# DSD_Aerobits_RPI4_OLED.net
KiCad netlist of a schematic drawn in Altium Designer
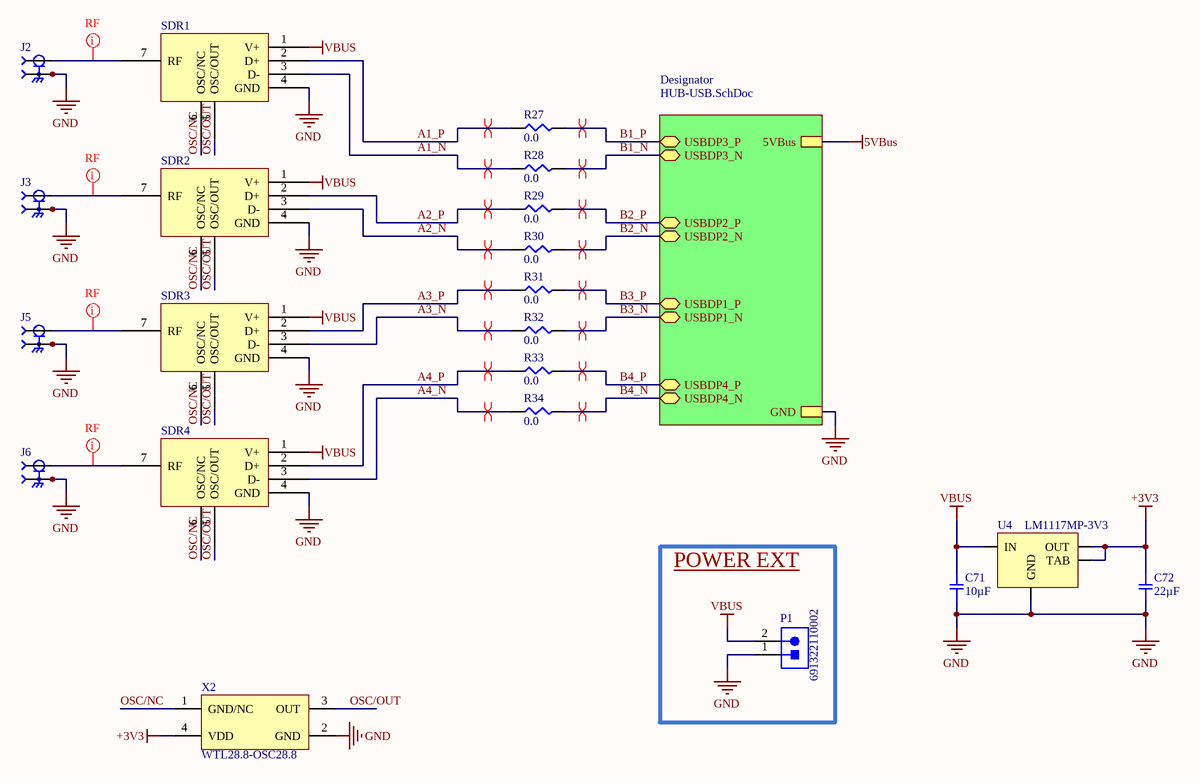
[diagram p0: DSD_Aerobits_RPI4_OLED.SchDoc]

(export (version "E")
  (design (tool "Eeschema 10.0.6"))
  (components
    (comp (ref "C71")
      (value "10µF")
      (footprint "SMD-0805C")
      (description "CAP CER 10UF 16V X6S 0805")
      (fields
        (field (name "PART NUMBER") "GRT21BC81C106KE01L")
        (field (name "DIGI-KEY PART NUMBER") "490-12343-1-ND")
      )
      (libsource (lib "cap_murata") (part "CAPACITOR"))
    )
    (comp (ref "C72")
      (value "22µF")
      (footprint "SMD-0805C")
      (description "CAP CER 22UF 16V X5R 0805")
      (fields
        (field (name "PART NUMBER") "GRT21BR61C226ME13L")
        (field (name "DIGI-KEY PART NUMBER") "490-12383-1-ND")
      )
      (libsource (lib "cap_murata") (part "CAPACITOR"))
    )
    (comp (ref "J2")
      (value "CON-SMA-EDGE-S")
      (footprint "RFSOLUTIONS_CON-SMA-EDGE-S")
      (description "SMA Connector Jack, Female Socket - Board Edge, End Launch Solder")
      (fields (field (name "MF") "RF Solutions") (field (name "DIGI-KEY_PART_NUMBER") "CON-SMA-EDGE-S-ND"))
      (libsource (lib "CON-SMA-EDGE-S") (part "CON-SMA-EDGE-S"))
    )
    (comp (ref "J3")
      (value "CON-SMA-EDGE-S")
      (footprint "RFSOLUTIONS_CON-SMA-EDGE-S")
      (description "SMA Connector Jack, Female Socket - Board Edge, End Launch Solder")
      (fields (field (name "MF") "RF Solutions") (field (name "DIGI-KEY_PART_NUMBER") "CON-SMA-EDGE-S-ND"))
      (libsource (lib "CON-SMA-EDGE-S") (part "CON-SMA-EDGE-S"))
    )
    (comp (ref "J5")
      (value "CON-SMA-EDGE-S")
      (footprint "RFSOLUTIONS_CON-SMA-EDGE-S")
      (description "SMA Connector Jack, Female Socket - Board Edge, End Launch Solder")
      (fields (field (name "MF") "RF Solutions") (field (name "DIGI-KEY_PART_NUMBER") "CON-SMA-EDGE-S-ND"))
      (libsource (lib "CON-SMA-EDGE-S") (part "CON-SMA-EDGE-S"))
    )
    (comp (ref "J6")
      (value "CON-SMA-EDGE-S")
      (footprint "RFSOLUTIONS_CON-SMA-EDGE-S")
      (description "SMA Connector Jack, Female Socket - Board Edge, End Launch Solder")
      (fields (field (name "MF") "RF Solutions") (field (name "DIGI-KEY_PART_NUMBER") "CON-SMA-EDGE-S-ND"))
      (libsource (lib "CON-SMA-EDGE-S") (part "CON-SMA-EDGE-S"))
    )
    (comp (ref "P1")
      (value "691322110002")
      (footprint "691322110002")
      (description "WR-TBL Serie 3221 Horizontal PCB Header, Pluggable, THT, pitch 3.5mm, 2p")
      (fields (field (name "MANUFACTURER") "Wurth Elektronik"))
      (libsource (lib "Altium_WR-TBL (rev21a)") (part "691322110002"))
    )
    (comp (ref "R27")
      (value "0.0")
      (footprint "SMD-0603-RES")
      (description "RES SMD 0.0OHM JUMPER 1/10W 0603")
      (fields (field (name "PART NUMBER") "ERJ-3GEY0R00V") (field (name "DIGI-KEY PART NUMBER") "P0.0GCT-ND"))
      (libsource (lib "res_panasonic_erj_xls") (part "RESISTOR"))
    )
    (comp (ref "R28")
      (value "0.0")
      (footprint "SMD-0603-RES")
      (description "RES SMD 0.0OHM JUMPER 1/10W 0603")
      (fields (field (name "PART NUMBER") "ERJ-3GEY0R00V") (field (name "DIGI-KEY PART NUMBER") "P0.0GCT-ND"))
      (libsource (lib "res_panasonic_erj_xls") (part "RESISTOR"))
    )
    (comp (ref "R29")
      (value "0.0")
      (footprint "SMD-0603-RES")
      (description "RES SMD 0.0OHM JUMPER 1/10W 0603")
      (fields (field (name "PART NUMBER") "ERJ-3GEY0R00V") (field (name "DIGI-KEY PART NUMBER") "P0.0GCT-ND"))
      (libsource (lib "res_panasonic_erj_xls") (part "RESISTOR"))
    )
    (comp (ref "R30")
      (value "0.0")
      (footprint "SMD-0603-RES")
      (description "RES SMD 0.0OHM JUMPER 1/10W 0603")
      (fields (field (name "PART NUMBER") "ERJ-3GEY0R00V") (field (name "DIGI-KEY PART NUMBER") "P0.0GCT-ND"))
      (libsource (lib "res_panasonic_erj_xls") (part "RESISTOR"))
    )
    (comp (ref "R31")
      (value "0.0")
      (footprint "SMD-0603-RES")
      (description "RES SMD 0.0OHM JUMPER 1/10W 0603")
      (fields (field (name "PART NUMBER") "ERJ-3GEY0R00V") (field (name "DIGI-KEY PART NUMBER") "P0.0GCT-ND"))
      (libsource (lib "res_panasonic_erj_xls") (part "RESISTOR"))
    )
    (comp (ref "R32")
      (value "0.0")
      (footprint "SMD-0603-RES")
      (description "RES SMD 0.0OHM JUMPER 1/10W 0603")
      (fields (field (name "PART NUMBER") "ERJ-3GEY0R00V") (field (name "DIGI-KEY PART NUMBER") "P0.0GCT-ND"))
      (libsource (lib "res_panasonic_erj_xls") (part "RESISTOR"))
    )
    (comp (ref "R33")
      (value "0.0")
      (footprint "SMD-0603-RES")
      (description "RES SMD 0.0OHM JUMPER 1/10W 0603")
      (fields (field (name "PART NUMBER") "ERJ-3GEY0R00V") (field (name "DIGI-KEY PART NUMBER") "P0.0GCT-ND"))
      (libsource (lib "res_panasonic_erj_xls") (part "RESISTOR"))
    )
    (comp (ref "R34")
      (value "0.0")
      (footprint "SMD-0603-RES")
      (description "RES SMD 0.0OHM JUMPER 1/10W 0603")
      (fields (field (name "PART NUMBER") "ERJ-3GEY0R00V") (field (name "DIGI-KEY PART NUMBER") "P0.0GCT-ND"))
      (libsource (lib "res_panasonic_erj_xls") (part "RESISTOR"))
    )
    (comp (ref "SDR1")
      (value "SDR_Module")
      (footprint "SDR")
      (libsource (lib "SDR_Module") (part "SDR_Module"))
    )
    (comp (ref "SDR2")
      (value "SDR_Module")
      (footprint "SDR")
      (libsource (lib "SDR_Module") (part "SDR_Module"))
    )
    (comp (ref "SDR3")
      (value "SDR_Module")
      (footprint "SDR")
      (libsource (lib "SDR_Module") (part "SDR_Module"))
    )
    (comp (ref "SDR4")
      (value "SDR_Module")
      (footprint "SDR")
      (libsource (lib "SDR_Module") (part "SDR_Module"))
    )
    (comp (ref "U4")
      (value "LM1117MP-3V3")
      (footprint "SOT223")
      (description "800mA Low-Dropout Linear Regulator")
      (fields
        (field (name "PARTNUMBER") "LM1117MP-3.3")
        (field (name "MANUFACTURER") "National Semiconductor")
        (field (name "PUBLISHER") "Altium Limited")
      )
      (libsource (lib "biblioteka_schematic") (part "LM1117MP-3V3"))
    )
    (comp (ref "X2")
      (value "WTL28.8-OSC28.8")
      (footprint "WTL28.8-OSC28.8")
      (libsource (lib "DSD_Aerobits_RPI4_OLED") (part "WTL28.8-OSC28.8"))
    )
  )
  (nets
    (net (code "1") (name "+3V3") (class "Default")
      (node (ref "C72") (pin "2") (pinfunction "2_2") (pintype "passive"))
      (node (ref "U4") (pin "2") (pinfunction "OUT_2") (pintype "power_in"))
      (node (ref "U4") (pin "4") (pinfunction "TAB_4") (pintype "power_in"))
      (node (ref "X2") (pin "4") (pinfunction "VDD_4") (pintype "passive"))
    )
    (net (code "2") (name "/A1_N") (class "Default")
      (node (ref "R28") (pin "1") (pinfunction "1_1") (pintype "passive"))
      (node (ref "SDR1") (pin "3") (pinfunction "D-_3") (pintype "passive"))
    )
    (net (code "3") (name "/A1_P") (class "Default")
      (node (ref "R27") (pin "1") (pinfunction "1_1") (pintype "passive"))
      (node (ref "SDR1") (pin "2") (pinfunction "D+_2") (pintype "passive"))
    )
    (net (code "4") (name "/A2_N") (class "Default")
      (node (ref "R30") (pin "1") (pinfunction "1_1") (pintype "passive"))
      (node (ref "SDR2") (pin "3") (pinfunction "D-_3") (pintype "passive"))
    )
    (net (code "5") (name "/A2_P") (class "Default")
      (node (ref "R29") (pin "1") (pinfunction "1_1") (pintype "passive"))
      (node (ref "SDR2") (pin "2") (pinfunction "D+_2") (pintype "passive"))
    )
    (net (code "6") (name "/A3_N") (class "Default")
      (node (ref "R32") (pin "1") (pinfunction "1_1") (pintype "passive"))
      (node (ref "SDR3") (pin "3") (pinfunction "D-_3") (pintype "passive"))
    )
    (net (code "7") (name "/A3_P") (class "Default")
      (node (ref "R31") (pin "1") (pinfunction "1_1") (pintype "passive"))
      (node (ref "SDR3") (pin "2") (pinfunction "D+_2") (pintype "passive"))
    )
    (net (code "8") (name "/A4_N") (class "Default")
      (node (ref "R34") (pin "1") (pinfunction "1_1") (pintype "passive"))
      (node (ref "SDR4") (pin "3") (pinfunction "D-_3") (pintype "passive"))
    )
    (net (code "9") (name "/A4_P") (class "Default")
      (node (ref "R33") (pin "1") (pinfunction "1_1") (pintype "passive"))
      (node (ref "SDR4") (pin "2") (pinfunction "D+_2") (pintype "passive"))
    )
    (net (code "10") (name "/B1_N") (class "Default")
      (node (ref "R28") (pin "2") (pinfunction "2_2") (pintype "passive"))
    )
    (net (code "11") (name "/B1_P") (class "Default")
      (node (ref "R27") (pin "2") (pinfunction "2_2") (pintype "passive"))
    )
    (net (code "12") (name "/B2_N") (class "Default")
      (node (ref "R30") (pin "2") (pinfunction "2_2") (pintype "passive"))
    )
    (net (code "13") (name "/B2_P") (class "Default")
      (node (ref "R29") (pin "2") (pinfunction "2_2") (pintype "passive"))
    )
    (net (code "14") (name "/B3_N") (class "Default")
      (node (ref "R32") (pin "2") (pinfunction "2_2") (pintype "passive"))
    )
    (net (code "15") (name "/B3_P") (class "Default")
      (node (ref "R31") (pin "2") (pinfunction "2_2") (pintype "passive"))
    )
    (net (code "16") (name "/B4_N") (class "Default")
      (node (ref "R34") (pin "2") (pinfunction "2_2") (pintype "passive"))
    )
    (net (code "17") (name "/B4_P") (class "Default")
      (node (ref "R33") (pin "2") (pinfunction "2_2") (pintype "passive"))
    )
    (net (code "18") (name "/OSC{slash}NC") (class "Default")
      (node (ref "SDR1") (pin "6") (pinfunction "OSC/NC_6") (pintype "passive"))
      (node (ref "SDR2") (pin "6") (pinfunction "OSC/NC_6") (pintype "passive"))
      (node (ref "SDR3") (pin "6") (pinfunction "OSC/NC_6") (pintype "passive"))
      (node (ref "SDR4") (pin "6") (pinfunction "OSC/NC_6") (pintype "passive"))
      (node (ref "X2") (pin "1") (pinfunction "GND/NC_1") (pintype "passive"))
    )
    (net (code "19") (name "/OSC{slash}OUT") (class "Default")
      (node (ref "SDR1") (pin "5") (pinfunction "OSC/OUT_5") (pintype "passive"))
      (node (ref "SDR2") (pin "5") (pinfunction "OSC/OUT_5") (pintype "passive"))
      (node (ref "SDR3") (pin "5") (pinfunction "OSC/OUT_5") (pintype "passive"))
      (node (ref "SDR4") (pin "5") (pinfunction "OSC/OUT_5") (pintype "passive"))
      (node (ref "X2") (pin "3") (pinfunction "OUT_3") (pintype "passive"))
    )
    (net (code "21") (name "GND") (class "Default")
      (node (ref "C71") (pin "1") (pinfunction "1_1") (pintype "passive"))
      (node (ref "C72") (pin "1") (pinfunction "1_1") (pintype "passive"))
      (node (ref "J2") (pin "G1") (pinfunction "2_G1") (pintype "passive"))
      (node (ref "J2") (pin "G2") (pinfunction "2_G2") (pintype "passive"))
      (node (ref "J2") (pin "G3") (pinfunction "2_G3") (pintype "passive"))
      (node (ref "J2") (pin "G4") (pinfunction "2_G4") (pintype "passive"))
      (node (ref "J3") (pin "G1") (pinfunction "2_G1") (pintype "passive"))
      (node (ref "J3") (pin "G2") (pinfunction "2_G2") (pintype "passive"))
      (node (ref "J3") (pin "G3") (pinfunction "2_G3") (pintype "passive"))
      (node (ref "J3") (pin "G4") (pinfunction "2_G4") (pintype "passive"))
      (node (ref "J5") (pin "G1") (pinfunction "2_G1") (pintype "passive"))
      (node (ref "J5") (pin "G2") (pinfunction "2_G2") (pintype "passive"))
      (node (ref "J5") (pin "G3") (pinfunction "2_G3") (pintype "passive"))
      (node (ref "J5") (pin "G4") (pinfunction "2_G4") (pintype "passive"))
      (node (ref "J6") (pin "G1") (pinfunction "2_G1") (pintype "passive"))
      (node (ref "J6") (pin "G2") (pinfunction "2_G2") (pintype "passive"))
      (node (ref "J6") (pin "G3") (pinfunction "2_G3") (pintype "passive"))
      (node (ref "J6") (pin "G4") (pinfunction "2_G4") (pintype "passive"))
      (node (ref "P1") (pin "1") (pinfunction "1_1") (pintype "passive"))
      (node (ref "SDR1") (pin "4") (pinfunction "GND_4") (pintype "passive"))
      (node (ref "SDR2") (pin "4") (pinfunction "GND_4") (pintype "passive"))
      (node (ref "SDR3") (pin "4") (pinfunction "GND_4") (pintype "passive"))
      (node (ref "SDR4") (pin "4") (pinfunction "GND_4") (pintype "passive"))
      (node (ref "U4") (pin "1") (pinfunction "GND_1") (pintype "power_in"))
      (node (ref "X2") (pin "2") (pinfunction "GND_2") (pintype "passive"))
    )
    (net (code "22") (name "Net-(SDR1-RF)") (class "Default")
      (node (ref "J2") (pin "1") (pinfunction "1_1") (pintype "passive"))
      (node (ref "SDR1") (pin "7") (pinfunction "RF_7") (pintype "passive"))
    )
    (net (code "23") (name "Net-(SDR2-RF)") (class "Default")
      (node (ref "J3") (pin "1") (pinfunction "1_1") (pintype "passive"))
      (node (ref "SDR2") (pin "7") (pinfunction "RF_7") (pintype "passive"))
    )
    (net (code "24") (name "Net-(SDR3-RF)") (class "Default")
      (node (ref "J5") (pin "1") (pinfunction "1_1") (pintype "passive"))
      (node (ref "SDR3") (pin "7") (pinfunction "RF_7") (pintype "passive"))
    )
    (net (code "25") (name "Net-(SDR4-RF)") (class "Default")
      (node (ref "J6") (pin "1") (pinfunction "1_1") (pintype "passive"))
      (node (ref "SDR4") (pin "7") (pinfunction "RF_7") (pintype "passive"))
    )
    (net (code "26") (name "VBUS") (class "Default")
      (node (ref "C71") (pin "2") (pinfunction "2_2") (pintype "passive"))
      (node (ref "P1") (pin "2") (pinfunction "2_2") (pintype "passive"))
      (node (ref "SDR1") (pin "1") (pinfunction "V+_1") (pintype "passive"))
      (node (ref "SDR2") (pin "1") (pinfunction "V+_1") (pintype "passive"))
      (node (ref "SDR3") (pin "1") (pinfunction "V+_1") (pintype "passive"))
      (node (ref "SDR4") (pin "1") (pinfunction "V+_1") (pintype "passive"))
      (node (ref "U4") (pin "3") (pinfunction "IN_3") (pintype "power_in"))
    )
  )
)
